# phonecard-reader.net
KiCad netlist of a schematic drawn in EAGLE
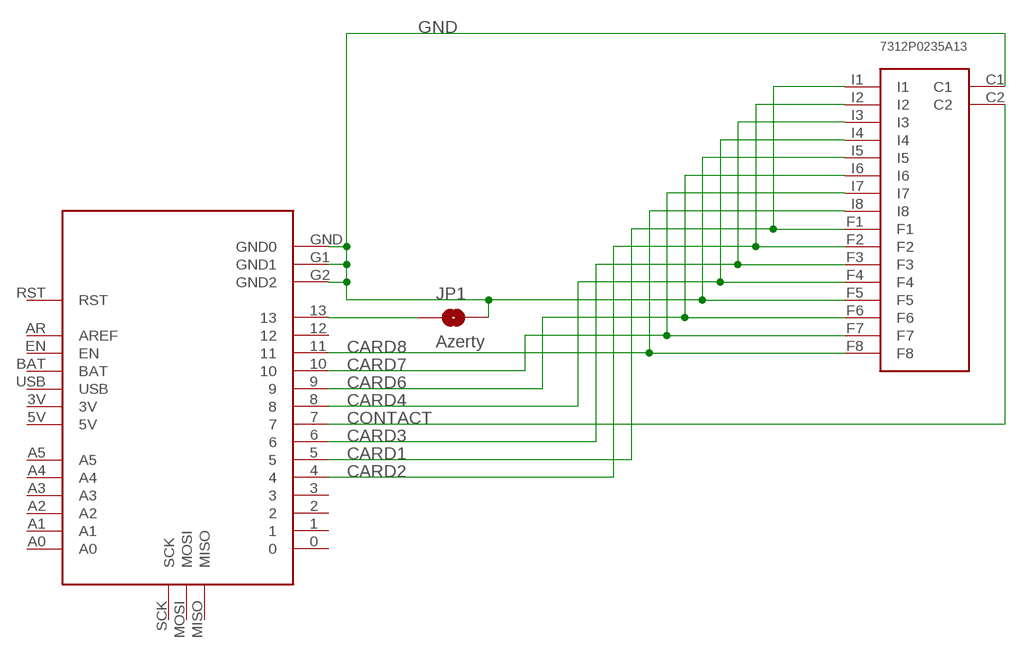
[diagram p0: schematic, sheet 1]

(export (version "E")
  (design (tool "Eeschema 10.0.6"))
  (components
    (comp (ref "JP1")
      (value "Azerty")
      (footprint "eagle-import:SMT-JUMPER_2_NO_SILK_ROUND")
      (libsource (lib "eagle-import") (part "JUMPER-SMT_2_NO_SILK_ROUND"))
    )
    (comp (ref "U$1")
      (value "Itsy Bitsy 5V")
      (footprint "eagle-import:ITSY_BITSY_SMD")
      (libsource (lib "eagle-import") (part "ITSY_BITSY"))
    )
    (comp (ref "U$2")
      (value "7312P0235A13LFC")
      (footprint "eagle-import:7312P0235A13")
      (libsource (lib "eagle-import") (part "7312P0235A13LFC"))
    )
  )
  (nets
    (net (code "1") (name "/CARD1") (class "Default")
      (node (ref "U$1") (pin "5") (pinfunction "5_5") (pintype "bidirectional"))
      (node (ref "U$2") (pin "F1") (pinfunction "F1_F1") (pintype "bidirectional"))
      (node (ref "U$2") (pin "I1") (pinfunction "I1_I1") (pintype "bidirectional"))
    )
    (net (code "2") (name "/CARD2") (class "Default")
      (node (ref "U$1") (pin "4") (pinfunction "4_4") (pintype "bidirectional"))
      (node (ref "U$2") (pin "F2") (pinfunction "F2_F2") (pintype "bidirectional"))
      (node (ref "U$2") (pin "I2") (pinfunction "I2_I2") (pintype "bidirectional"))
    )
    (net (code "3") (name "/CARD3") (class "Default")
      (node (ref "U$1") (pin "6") (pinfunction "6_6") (pintype "bidirectional"))
      (node (ref "U$2") (pin "F3") (pinfunction "F3_F3") (pintype "bidirectional"))
      (node (ref "U$2") (pin "I3") (pinfunction "I3_I3") (pintype "bidirectional"))
    )
    (net (code "4") (name "/CARD4") (class "Default")
      (node (ref "U$1") (pin "8") (pinfunction "8_8") (pintype "bidirectional"))
      (node (ref "U$2") (pin "F4") (pinfunction "F4_F4") (pintype "bidirectional"))
      (node (ref "U$2") (pin "I4") (pinfunction "I4_I4") (pintype "bidirectional"))
    )
    (net (code "5") (name "/CARD6") (class "Default")
      (node (ref "U$1") (pin "9") (pinfunction "9_9") (pintype "bidirectional"))
      (node (ref "U$2") (pin "F6") (pinfunction "F6_F6") (pintype "bidirectional"))
      (node (ref "U$2") (pin "I6") (pinfunction "I6_I6") (pintype "bidirectional"))
    )
    (net (code "6") (name "/CARD7") (class "Default")
      (node (ref "U$1") (pin "10") (pinfunction "10_10") (pintype "bidirectional"))
      (node (ref "U$2") (pin "F7") (pinfunction "F7_F7") (pintype "bidirectional"))
      (node (ref "U$2") (pin "I7") (pinfunction "I7_I7") (pintype "bidirectional"))
    )
    (net (code "7") (name "/CARD8") (class "Default")
      (node (ref "U$1") (pin "11") (pinfunction "11_11") (pintype "bidirectional"))
      (node (ref "U$2") (pin "F8") (pinfunction "F8_F8") (pintype "bidirectional"))
      (node (ref "U$2") (pin "I8") (pinfunction "I8_I8") (pintype "bidirectional"))
    )
    (net (code "8") (name "/CONTACT") (class "Default")
      (node (ref "U$1") (pin "7") (pinfunction "7_7") (pintype "bidirectional"))
      (node (ref "U$2") (pin "C2") (pinfunction "C2_C2") (pintype "bidirectional"))
    )
    (net (code "9") (name "/GND") (class "Default")
      (node (ref "JP1") (pin "2") (pinfunction "2_2") (pintype "passive"))
      (node (ref "U$1") (pin "G1") (pinfunction "GND1_G1") (pintype "bidirectional"))
      (node (ref "U$1") (pin "G2") (pinfunction "GND2_G2") (pintype "bidirectional"))
      (node (ref "U$1") (pin "GND") (pinfunction "GND0_GND") (pintype "bidirectional"))
      (node (ref "U$2") (pin "C1") (pinfunction "C1_C1") (pintype "bidirectional"))
      (node (ref "U$2") (pin "F5") (pinfunction "F5_F5") (pintype "bidirectional"))
      (node (ref "U$2") (pin "I5") (pinfunction "I5_I5") (pintype "bidirectional"))
    )
    (net (code "10") (name "Net-(JP1-Pad1)") (class "Default")
      (node (ref "JP1") (pin "1") (pinfunction "1_1") (pintype "passive"))
      (node (ref "U$1") (pin "13") (pinfunction "13_13") (pintype "bidirectional"))
    )
    (net (code "11") (name "unconnected-(U$1-AREF-PadAR)") (class "Default")
      (node (ref "U$1") (pin "AR") (pinfunction "AREF_AR") (pintype "bidirectional"))
    )
    (net (code "12") (name "unconnected-(U$1-Pad0)") (class "Default")
      (node (ref "U$1") (pin "0") (pinfunction "0_0") (pintype "bidirectional"))
    )
    (net (code "13") (name "unconnected-(U$1-Pad1)") (class "Default")
      (node (ref "U$1") (pin "1") (pinfunction "1_1") (pintype "bidirectional"))
    )
    (net (code "14") (name "unconnected-(U$1-Pad2)") (class "Default")
      (node (ref "U$1") (pin "2") (pinfunction "2_2") (pintype "bidirectional"))
    )
    (net (code "15") (name "unconnected-(U$1-Pad3)") (class "Default")
      (node (ref "U$1") (pin "3") (pinfunction "3_3") (pintype "bidirectional"))
    )
    (net (code "16") (name "unconnected-(U$1-Pad3V)") (class "Default")
      (node (ref "U$1") (pin "3V") (pinfunction "3V_3V") (pintype "bidirectional"))
    )
    (net (code "17") (name "unconnected-(U$1-Pad5V)") (class "Default")
      (node (ref "U$1") (pin "5V") (pinfunction "5V_5V") (pintype "bidirectional"))
    )
    (net (code "18") (name "unconnected-(U$1-Pad12)") (class "Default")
      (node (ref "U$1") (pin "12") (pinfunction "12_12") (pintype "bidirectional"))
    )
    (net (code "19") (name "unconnected-(U$1-PadA0)") (class "Default")
      (node (ref "U$1") (pin "A0") (pinfunction "A0_A0") (pintype "bidirectional"))
    )
    (net (code "20") (name "unconnected-(U$1-PadA1)") (class "Default")
      (node (ref "U$1") (pin "A1") (pinfunction "A1_A1") (pintype "bidirectional"))
    )
    (net (code "21") (name "unconnected-(U$1-PadA2)") (class "Default")
      (node (ref "U$1") (pin "A2") (pinfunction "A2_A2") (pintype "bidirectional"))
    )
    (net (code "22") (name "unconnected-(U$1-PadA3)") (class "Default")
      (node (ref "U$1") (pin "A3") (pinfunction "A3_A3") (pintype "bidirectional"))
    )
    (net (code "23") (name "unconnected-(U$1-PadA4)") (class "Default")
      (node (ref "U$1") (pin "A4") (pinfunction "A4_A4") (pintype "bidirectional"))
    )
    (net (code "24") (name "unconnected-(U$1-PadA5)") (class "Default")
      (node (ref "U$1") (pin "A5") (pinfunction "A5_A5") (pintype "bidirectional"))
    )
    (net (code "25") (name "unconnected-(U$1-PadBAT)") (class "Default")
      (node (ref "U$1") (pin "BAT") (pinfunction "BAT_BAT") (pintype "bidirectional"))
    )
    (net (code "26") (name "unconnected-(U$1-PadEN)") (class "Default")
      (node (ref "U$1") (pin "EN") (pinfunction "EN_EN") (pintype "bidirectional"))
    )
    (net (code "27") (name "unconnected-(U$1-PadMISO)") (class "Default")
      (node (ref "U$1") (pin "MISO") (pinfunction "MISO_MISO") (pintype "bidirectional"))
    )
    (net (code "28") (name "unconnected-(U$1-PadMOSI)") (class "Default")
      (node (ref "U$1") (pin "MOSI") (pinfunction "MOSI_MOSI") (pintype "bidirectional"))
    )
    (net (code "29") (name "unconnected-(U$1-PadRST)") (class "Default")
      (node (ref "U$1") (pin "RST") (pinfunction "RST_RST") (pintype "bidirectional"))
    )
    (net (code "30") (name "unconnected-(U$1-PadSCK)") (class "Default")
      (node (ref "U$1") (pin "SCK") (pinfunction "SCK_SCK") (pintype "bidirectional"))
    )
    (net (code "31") (name "unconnected-(U$1-PadUSB)") (class "Default")
      (node (ref "U$1") (pin "USB") (pinfunction "USB_USB") (pintype "bidirectional"))
    )
  )
)
